# schematic-simple-power-native.net
KiCad netlist of a schematic drawn in EasyEDA
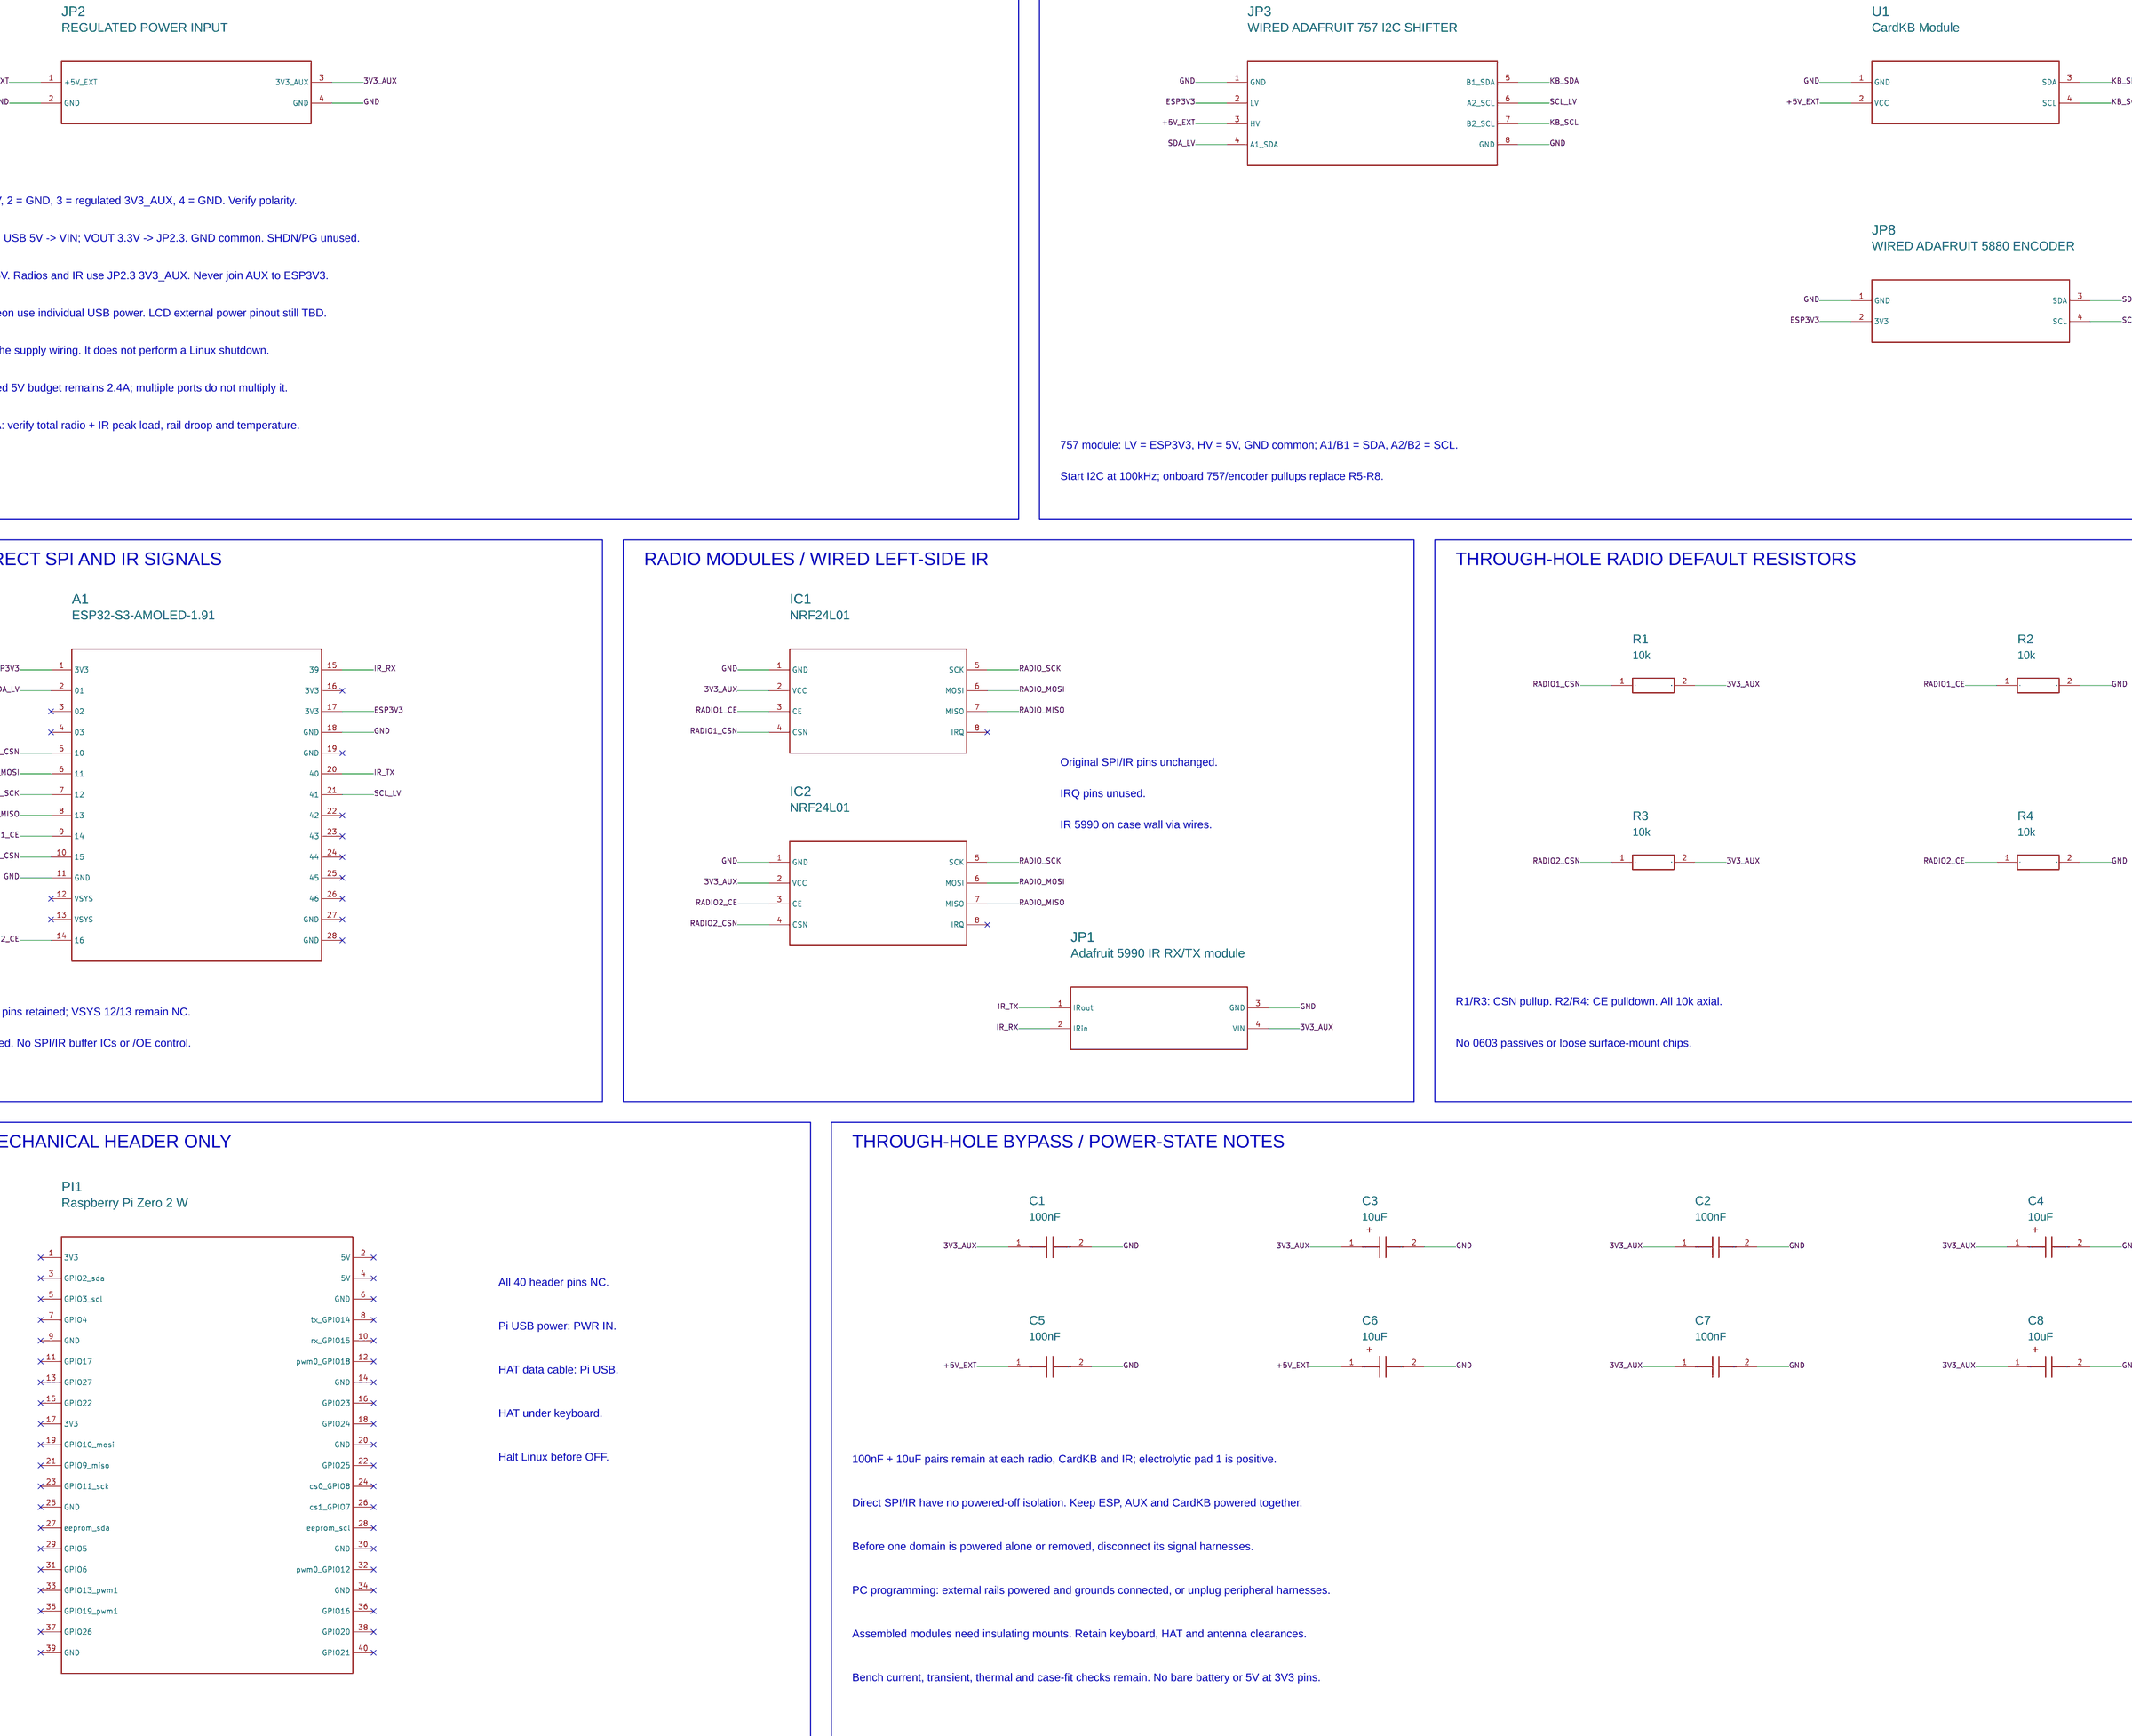
[diagram p0: schematic sheet]

(export (version "E")
  (design (tool "Eeschema 10.0.6"))
  (components
    (comp (ref "A1")
      (value "ESP32-S3-AMOLED-1.91")
      (fields (field (name "Manufacturer Part") "T-Display S3 AMOLED") (field (name "Manufacturer") "Lilygo"))
      (libsource (lib "") (part "ESP32-S3-AMOLED-1.91"))
    )
    (comp (ref "C1") (value "100nF") (libsource (lib "") (part "Ceramic capacitor 100nf 50V")))
    (comp (ref "C2") (value "100nF") (libsource (lib "") (part "Ceramic capacitor 100nf 50V")))
    (comp (ref "C3") (value "10uF") (libsource (lib "") (part "Capacitor 10uF TH")))
    (comp (ref "C4") (value "10uF") (libsource (lib "") (part "Capacitor 10uF TH")))
    (comp (ref "C5") (value "100nF") (libsource (lib "") (part "Ceramic capacitor 100nf 50V")))
    (comp (ref "C6") (value "10uF") (libsource (lib "") (part "Capacitor 10uF TH")))
    (comp (ref "C7") (value "100nF") (libsource (lib "") (part "Ceramic capacitor 100nf 50V")))
    (comp (ref "C8") (value "10uF") (libsource (lib "") (part "Capacitor 10uF TH")))
    (comp (ref "IC1") (value "NRF24L01") (libsource (lib "") (part "NRF24L01")))
    (comp (ref "IC2") (value "NRF24L01") (libsource (lib "") (part "NRF24L01")))
    (comp (ref "JP1") (value "Adafruit 5990 IR RX/TX module") (libsource (lib "") (part "M04_1")))
    (comp (ref "JP2") (value "REGULATED POWER INPUT") (libsource (lib "") (part "M04")))
    (comp (ref "JP3")
      (value "WIRED ADAFRUIT 757 I2C SHIFTER")
      (fields (field (name "Manufacturer Part") "THROUGH-HOLE WIRE HARNESS"))
      (libsource (lib "") (part "WIRED ADAFRUIT 757 I2C SHIFTER"))
    )
    (comp (ref "JP8")
      (value "WIRED ADAFRUIT 5880 ENCODER")
      (fields (field (name "Manufacturer Part") "THROUGH-HOLE WIRE HARNESS"))
      (libsource (lib "") (part "WIRED ADAFRUIT 5880 ENCODER"))
    )
    (comp (ref "PI1") (value "Raspberry Pi Zero 2 W") (libsource (lib "") (part "PI ZERO2 WDADAD")))
    (comp (ref "R1") (value "10k") (libsource (lib "") (part "Resistor")))
    (comp (ref "R2") (value "10k") (libsource (lib "") (part "Resistor")))
    (comp (ref "R3") (value "10k") (libsource (lib "") (part "Resistor")))
    (comp (ref "R4") (value "10k") (libsource (lib "") (part "Resistor")))
    (comp (ref "U1")
      (value "CardKB Module")
      (fields (field (name "Manufacturer Part") "CardKB") (field (name "Manufacturer") "M5Stack"))
      (libsource (lib "") (part "CardKB Module"))
    )
  )
  (nets
    (net (code "1") (name "/+5V_EXT") (class "Default")
      (node (ref "C5") (pin "1") (pinfunction "1_1") (pintype "unspecified"))
      (node (ref "C6") (pin "1") (pinfunction "1_1") (pintype "unspecified"))
      (node (ref "JP2") (pin "1") (pinfunction "+5V_EXT_1") (pintype "unspecified"))
      (node (ref "JP3") (pin "3") (pinfunction "HV_3") (pintype "unspecified"))
      (node (ref "U1") (pin "2") (pinfunction "VCC_2") (pintype "unspecified"))
    )
    (net (code "2") (name "/3V3_AUX") (class "Default")
      (node (ref "C1") (pin "1") (pinfunction "1_1") (pintype "unspecified"))
      (node (ref "C2") (pin "1") (pinfunction "1_1") (pintype "unspecified"))
      (node (ref "C3") (pin "1") (pinfunction "1_1") (pintype "unspecified"))
      (node (ref "C4") (pin "1") (pinfunction "1_1") (pintype "unspecified"))
      (node (ref "C7") (pin "1") (pinfunction "1_1") (pintype "unspecified"))
      (node (ref "C8") (pin "1") (pinfunction "1_1") (pintype "unspecified"))
      (node (ref "IC1") (pin "2") (pinfunction "VCC_2") (pintype "unspecified"))
      (node (ref "IC2") (pin "2") (pinfunction "VCC_2") (pintype "unspecified"))
      (node (ref "JP1") (pin "4") (pinfunction "VIN_4") (pintype "unspecified"))
      (node (ref "JP2") (pin "3") (pinfunction "3V3_AUX_3") (pintype "unspecified"))
      (node (ref "R1") (pin "2") (pinfunction "2_2") (pintype "unspecified"))
      (node (ref "R3") (pin "2") (pinfunction "2_2") (pintype "unspecified"))
    )
    (net (code "3") (name "/ESP3V3") (class "Default")
      (node (ref "A1") (pin "1") (pinfunction "3V3_1") (pintype "unspecified"))
      (node (ref "A1") (pin "17") (pinfunction "3V3_17") (pintype "unspecified"))
      (node (ref "JP3") (pin "2") (pinfunction "LV_2") (pintype "unspecified"))
      (node (ref "JP8") (pin "2") (pinfunction "3V3_2") (pintype "unspecified"))
    )
    (net (code "4") (name "/GND") (class "Default")
      (node (ref "A1") (pin "11") (pinfunction "GND_11") (pintype "unspecified"))
      (node (ref "A1") (pin "18") (pinfunction "GND_18") (pintype "unspecified"))
      (node (ref "C1") (pin "2") (pinfunction "2_2") (pintype "unspecified"))
      (node (ref "C2") (pin "2") (pinfunction "2_2") (pintype "unspecified"))
      (node (ref "C3") (pin "2") (pinfunction "2_2") (pintype "unspecified"))
      (node (ref "C4") (pin "2") (pinfunction "2_2") (pintype "unspecified"))
      (node (ref "C5") (pin "2") (pinfunction "2_2") (pintype "unspecified"))
      (node (ref "C6") (pin "2") (pinfunction "2_2") (pintype "unspecified"))
      (node (ref "C7") (pin "2") (pinfunction "2_2") (pintype "unspecified"))
      (node (ref "C8") (pin "2") (pinfunction "2_2") (pintype "unspecified"))
      (node (ref "IC1") (pin "1") (pinfunction "GND_1") (pintype "unspecified"))
      (node (ref "IC2") (pin "1") (pinfunction "GND_1") (pintype "unspecified"))
      (node (ref "JP1") (pin "3") (pinfunction "GND_3") (pintype "unspecified"))
      (node (ref "JP2") (pin "2") (pinfunction "GND_2") (pintype "unspecified"))
      (node (ref "JP2") (pin "4") (pinfunction "GND_4") (pintype "unspecified"))
      (node (ref "JP3") (pin "1") (pinfunction "GND_1") (pintype "unspecified"))
      (node (ref "JP3") (pin "8") (pinfunction "GND_8") (pintype "unspecified"))
      (node (ref "JP8") (pin "1") (pinfunction "GND_1") (pintype "unspecified"))
      (node (ref "R2") (pin "2") (pinfunction "2_2") (pintype "unspecified"))
      (node (ref "R4") (pin "2") (pinfunction "2_2") (pintype "unspecified"))
      (node (ref "U1") (pin "1") (pinfunction "GND_1") (pintype "unspecified"))
    )
    (net (code "5") (name "/IR_RX") (class "Default")
      (node (ref "A1") (pin "15") (pinfunction "39_15") (pintype "unspecified"))
      (node (ref "JP1") (pin "2") (pinfunction "IRin_2") (pintype "unspecified"))
    )
    (net (code "6") (name "/IR_TX") (class "Default")
      (node (ref "A1") (pin "20") (pinfunction "40_20") (pintype "unspecified"))
      (node (ref "JP1") (pin "1") (pinfunction "IRout_1") (pintype "unspecified"))
    )
    (net (code "7") (name "/KB_SCL") (class "Default")
      (node (ref "JP3") (pin "7") (pinfunction "B2_SCL_7") (pintype "unspecified"))
      (node (ref "U1") (pin "4") (pinfunction "SCL_4") (pintype "unspecified"))
    )
    (net (code "8") (name "/KB_SDA") (class "Default")
      (node (ref "JP3") (pin "5") (pinfunction "B1_SDA_5") (pintype "unspecified"))
      (node (ref "U1") (pin "3") (pinfunction "SDA_3") (pintype "unspecified"))
    )
    (net (code "9") (name "/RADIO1_CE") (class "Default")
      (node (ref "A1") (pin "9") (pinfunction "14_9") (pintype "unspecified"))
      (node (ref "IC1") (pin "3") (pinfunction "CE_3") (pintype "unspecified"))
      (node (ref "R2") (pin "1") (pinfunction "1_1") (pintype "unspecified"))
    )
    (net (code "10") (name "/RADIO1_CSN") (class "Default")
      (node (ref "A1") (pin "5") (pinfunction "10_5") (pintype "unspecified"))
      (node (ref "IC1") (pin "4") (pinfunction "CSN_4") (pintype "unspecified"))
      (node (ref "R1") (pin "1") (pinfunction "1_1") (pintype "unspecified"))
    )
    (net (code "11") (name "/RADIO2_CE") (class "Default")
      (node (ref "A1") (pin "14") (pinfunction "16_14") (pintype "unspecified"))
      (node (ref "IC2") (pin "3") (pinfunction "CE_3") (pintype "unspecified"))
      (node (ref "R4") (pin "1") (pinfunction "1_1") (pintype "unspecified"))
    )
    (net (code "12") (name "/RADIO2_CSN") (class "Default")
      (node (ref "A1") (pin "10") (pinfunction "15_10") (pintype "unspecified"))
      (node (ref "IC2") (pin "4") (pinfunction "CSN_4") (pintype "unspecified"))
      (node (ref "R3") (pin "1") (pinfunction "1_1") (pintype "unspecified"))
    )
    (net (code "13") (name "/RADIO_MISO") (class "Default")
      (node (ref "A1") (pin "8") (pinfunction "13_8") (pintype "unspecified"))
      (node (ref "IC1") (pin "7") (pinfunction "MISO_7") (pintype "unspecified"))
      (node (ref "IC2") (pin "7") (pinfunction "MISO_7") (pintype "unspecified"))
    )
    (net (code "14") (name "/RADIO_MOSI") (class "Default")
      (node (ref "A1") (pin "6") (pinfunction "11_6") (pintype "unspecified"))
      (node (ref "IC1") (pin "6") (pinfunction "MOSI_6") (pintype "unspecified"))
      (node (ref "IC2") (pin "6") (pinfunction "MOSI_6") (pintype "unspecified"))
    )
    (net (code "15") (name "/RADIO_SCK") (class "Default")
      (node (ref "A1") (pin "7") (pinfunction "12_7") (pintype "unspecified"))
      (node (ref "IC1") (pin "5") (pinfunction "SCK_5") (pintype "unspecified"))
      (node (ref "IC2") (pin "5") (pinfunction "SCK_5") (pintype "unspecified"))
    )
    (net (code "16") (name "/SCL_LV") (class "Default")
      (node (ref "A1") (pin "21") (pinfunction "41_21") (pintype "unspecified"))
      (node (ref "JP3") (pin "6") (pinfunction "A2_SCL_6") (pintype "unspecified"))
      (node (ref "JP8") (pin "4") (pinfunction "SCL_4") (pintype "unspecified"))
    )
    (net (code "17") (name "/SDA_LV") (class "Default")
      (node (ref "A1") (pin "2") (pinfunction "01_2") (pintype "unspecified"))
      (node (ref "JP3") (pin "4") (pinfunction "A1_SDA_4") (pintype "unspecified"))
      (node (ref "JP8") (pin "3") (pinfunction "SDA_3") (pintype "unspecified"))
    )
    (net (code "18") (name "unconnected-(A1-02-Pad3)") (class "Default")
      (node (ref "A1") (pin "3") (pinfunction "02_3") (pintype "unspecified+no_connect"))
    )
    (net (code "19") (name "unconnected-(A1-03-Pad4)") (class "Default")
      (node (ref "A1") (pin "4") (pinfunction "03_4") (pintype "unspecified+no_connect"))
    )
    (net (code "20") (name "unconnected-(A1-3V3-Pad16)") (class "Default")
      (node (ref "A1") (pin "16") (pinfunction "3V3_16") (pintype "unspecified+no_connect"))
    )
    (net (code "21") (name "unconnected-(A1-42-Pad22)") (class "Default")
      (node (ref "A1") (pin "22") (pinfunction "42_22") (pintype "unspecified+no_connect"))
    )
    (net (code "22") (name "unconnected-(A1-43-Pad23)") (class "Default")
      (node (ref "A1") (pin "23") (pinfunction "43_23") (pintype "unspecified+no_connect"))
    )
    (net (code "23") (name "unconnected-(A1-44-Pad24)") (class "Default")
      (node (ref "A1") (pin "24") (pinfunction "44_24") (pintype "unspecified+no_connect"))
    )
    (net (code "24") (name "unconnected-(A1-45-Pad25)") (class "Default")
      (node (ref "A1") (pin "25") (pinfunction "45_25") (pintype "unspecified+no_connect"))
    )
    (net (code "25") (name "unconnected-(A1-46-Pad26)") (class "Default")
      (node (ref "A1") (pin "26") (pinfunction "46_26") (pintype "unspecified+no_connect"))
    )
    (net (code "26") (name "unconnected-(A1-GND-Pad19)") (class "Default")
      (node (ref "A1") (pin "19") (pinfunction "GND_19") (pintype "unspecified+no_connect"))
    )
    (net (code "27") (name "unconnected-(A1-GND-Pad27)") (class "Default")
      (node (ref "A1") (pin "27") (pinfunction "GND_27") (pintype "unspecified+no_connect"))
    )
    (net (code "28") (name "unconnected-(A1-GND-Pad28)") (class "Default")
      (node (ref "A1") (pin "28") (pinfunction "GND_28") (pintype "unspecified+no_connect"))
    )
    (net (code "29") (name "unconnected-(A1-VSYS-Pad12)") (class "Default")
      (node (ref "A1") (pin "12") (pinfunction "VSYS_12") (pintype "unspecified+no_connect"))
    )
    (net (code "30") (name "unconnected-(A1-VSYS-Pad13)") (class "Default")
      (node (ref "A1") (pin "13") (pinfunction "VSYS_13") (pintype "unspecified+no_connect"))
    )
    (net (code "31") (name "unconnected-(IC1-IRQ-Pad8)") (class "Default")
      (node (ref "IC1") (pin "8") (pinfunction "IRQ_8") (pintype "unspecified+no_connect"))
    )
    (net (code "32") (name "unconnected-(IC2-IRQ-Pad8)") (class "Default")
      (node (ref "IC2") (pin "8") (pinfunction "IRQ_8") (pintype "unspecified+no_connect"))
    )
    (net (code "33") (name "unconnected-(PI1-3V3-Pad1)") (class "Default")
      (node (ref "PI1") (pin "1") (pinfunction "3V3_1") (pintype "unspecified+no_connect"))
    )
    (net (code "34") (name "unconnected-(PI1-3V3-Pad17)") (class "Default")
      (node (ref "PI1") (pin "17") (pinfunction "3V3_17") (pintype "unspecified+no_connect"))
    )
    (net (code "35") (name "unconnected-(PI1-5V-Pad2)") (class "Default")
      (node (ref "PI1") (pin "2") (pinfunction "5V_2") (pintype "unspecified+no_connect"))
    )
    (net (code "36") (name "unconnected-(PI1-5V-Pad4)") (class "Default")
      (node (ref "PI1") (pin "4") (pinfunction "5V_4") (pintype "unspecified+no_connect"))
    )
    (net (code "37") (name "unconnected-(PI1-GND-Pad6)") (class "Default")
      (node (ref "PI1") (pin "6") (pinfunction "GND_6") (pintype "unspecified+no_connect"))
    )
    (net (code "38") (name "unconnected-(PI1-GND-Pad9)") (class "Default")
      (node (ref "PI1") (pin "9") (pinfunction "GND_9") (pintype "unspecified+no_connect"))
    )
    (net (code "39") (name "unconnected-(PI1-GND-Pad14)") (class "Default")
      (node (ref "PI1") (pin "14") (pinfunction "GND_14") (pintype "unspecified+no_connect"))
    )
    (net (code "40") (name "unconnected-(PI1-GND-Pad20)") (class "Default")
      (node (ref "PI1") (pin "20") (pinfunction "GND_20") (pintype "unspecified+no_connect"))
    )
    (net (code "41") (name "unconnected-(PI1-GND-Pad25)") (class "Default")
      (node (ref "PI1") (pin "25") (pinfunction "GND_25") (pintype "unspecified+no_connect"))
    )
    (net (code "42") (name "unconnected-(PI1-GND-Pad30)") (class "Default")
      (node (ref "PI1") (pin "30") (pinfunction "GND_30") (pintype "unspecified+no_connect"))
    )
    (net (code "43") (name "unconnected-(PI1-GND-Pad34)") (class "Default")
      (node (ref "PI1") (pin "34") (pinfunction "GND_34") (pintype "unspecified+no_connect"))
    )
    (net (code "44") (name "unconnected-(PI1-GND-Pad39)") (class "Default")
      (node (ref "PI1") (pin "39") (pinfunction "GND_39") (pintype "unspecified+no_connect"))
    )
    (net (code "45") (name "unconnected-(PI1-GPIO2_sda-Pad3)") (class "Default")
      (node (ref "PI1") (pin "3") (pinfunction "GPIO2_sda_3") (pintype "unspecified+no_connect"))
    )
    (net (code "46") (name "unconnected-(PI1-GPIO3_scl-Pad5)") (class "Default")
      (node (ref "PI1") (pin "5") (pinfunction "GPIO3_scl_5") (pintype "unspecified+no_connect"))
    )
    (net (code "47") (name "unconnected-(PI1-GPIO4-Pad7)") (class "Default")
      (node (ref "PI1") (pin "7") (pinfunction "GPIO4_7") (pintype "unspecified+no_connect"))
    )
    (net (code "48") (name "unconnected-(PI1-GPIO5-Pad29)") (class "Default")
      (node (ref "PI1") (pin "29") (pinfunction "GPIO5_29") (pintype "unspecified+no_connect"))
    )
    (net (code "49") (name "unconnected-(PI1-GPIO6-Pad31)") (class "Default")
      (node (ref "PI1") (pin "31") (pinfunction "GPIO6_31") (pintype "unspecified+no_connect"))
    )
    (net (code "50") (name "unconnected-(PI1-GPIO9_miso-Pad21)") (class "Default")
      (node (ref "PI1") (pin "21") (pinfunction "GPIO9_miso_21") (pintype "unspecified+no_connect"))
    )
    (net (code "51") (name "unconnected-(PI1-GPIO10_mosi-Pad19)") (class "Default")
      (node (ref "PI1") (pin "19") (pinfunction "GPIO10_mosi_19") (pintype "unspecified+no_connect"))
    )
    (net (code "52") (name "unconnected-(PI1-GPIO11_sck-Pad23)") (class "Default")
      (node (ref "PI1") (pin "23") (pinfunction "GPIO11_sck_23") (pintype "unspecified+no_connect"))
    )
    (net (code "53") (name "unconnected-(PI1-GPIO13_pwm1-Pad33)") (class "Default")
      (node (ref "PI1") (pin "33") (pinfunction "GPIO13_pwm1_33") (pintype "unspecified+no_connect"))
    )
    (net (code "54") (name "unconnected-(PI1-GPIO16-Pad36)") (class "Default")
      (node (ref "PI1") (pin "36") (pinfunction "GPIO16_36") (pintype "unspecified+no_connect"))
    )
    (net (code "55") (name "unconnected-(PI1-GPIO17-Pad11)") (class "Default")
      (node (ref "PI1") (pin "11") (pinfunction "GPIO17_11") (pintype "unspecified+no_connect"))
    )
    (net (code "56") (name "unconnected-(PI1-GPIO19_pwm1-Pad35)") (class "Default")
      (node (ref "PI1") (pin "35") (pinfunction "GPIO19_pwm1_35") (pintype "unspecified+no_connect"))
    )
    (net (code "57") (name "unconnected-(PI1-GPIO20-Pad38)") (class "Default")
      (node (ref "PI1") (pin "38") (pinfunction "GPIO20_38") (pintype "unspecified+no_connect"))
    )
    (net (code "58") (name "unconnected-(PI1-GPIO21-Pad40)") (class "Default")
      (node (ref "PI1") (pin "40") (pinfunction "GPIO21_40") (pintype "unspecified+no_connect"))
    )
    (net (code "59") (name "unconnected-(PI1-GPIO22-Pad15)") (class "Default")
      (node (ref "PI1") (pin "15") (pinfunction "GPIO22_15") (pintype "unspecified+no_connect"))
    )
    (net (code "60") (name "unconnected-(PI1-GPIO23-Pad16)") (class "Default")
      (node (ref "PI1") (pin "16") (pinfunction "GPIO23_16") (pintype "unspecified+no_connect"))
    )
    (net (code "61") (name "unconnected-(PI1-GPIO24-Pad18)") (class "Default")
      (node (ref "PI1") (pin "18") (pinfunction "GPIO24_18") (pintype "unspecified+no_connect"))
    )
    (net (code "62") (name "unconnected-(PI1-GPIO25-Pad22)") (class "Default")
      (node (ref "PI1") (pin "22") (pinfunction "GPIO25_22") (pintype "unspecified+no_connect"))
    )
    (net (code "63") (name "unconnected-(PI1-GPIO26-Pad37)") (class "Default")
      (node (ref "PI1") (pin "37") (pinfunction "GPIO26_37") (pintype "unspecified+no_connect"))
    )
    (net (code "64") (name "unconnected-(PI1-GPIO27-Pad13)") (class "Default")
      (node (ref "PI1") (pin "13") (pinfunction "GPIO27_13") (pintype "unspecified+no_connect"))
    )
    (net (code "65") (name "unconnected-(PI1-cs0_GPIO8-Pad24)") (class "Default")
      (node (ref "PI1") (pin "24") (pinfunction "cs0_GPIO8_24") (pintype "unspecified+no_connect"))
    )
    (net (code "66") (name "unconnected-(PI1-cs1_GPIO7-Pad26)") (class "Default")
      (node (ref "PI1") (pin "26") (pinfunction "cs1_GPIO7_26") (pintype "unspecified+no_connect"))
    )
    (net (code "67") (name "unconnected-(PI1-eeprom_scl-Pad28)") (class "Default")
      (node (ref "PI1") (pin "28") (pinfunction "eeprom_scl_28") (pintype "unspecified+no_connect"))
    )
    (net (code "68") (name "unconnected-(PI1-eeprom_sda-Pad27)") (class "Default")
      (node (ref "PI1") (pin "27") (pinfunction "eeprom_sda_27") (pintype "unspecified+no_connect"))
    )
    (net (code "69") (name "unconnected-(PI1-pwm0_GPIO12-Pad32)") (class "Default")
      (node (ref "PI1") (pin "32") (pinfunction "pwm0_GPIO12_32") (pintype "unspecified+no_connect"))
    )
    (net (code "70") (name "unconnected-(PI1-pwm0_GPIO18-Pad12)") (class "Default")
      (node (ref "PI1") (pin "12") (pinfunction "pwm0_GPIO18_12") (pintype "unspecified+no_connect"))
    )
    (net (code "71") (name "unconnected-(PI1-rx_GPIO15-Pad10)") (class "Default")
      (node (ref "PI1") (pin "10") (pinfunction "rx_GPIO15_10") (pintype "unspecified+no_connect"))
    )
    (net (code "72") (name "unconnected-(PI1-tx_GPIO14-Pad8)") (class "Default")
      (node (ref "PI1") (pin "8") (pinfunction "tx_GPIO14_8") (pintype "unspecified+no_connect"))
    )
  )
)
